# Optocoupler_STM32_REVA.net
KiCad netlist of a schematic drawn in Altium Designer
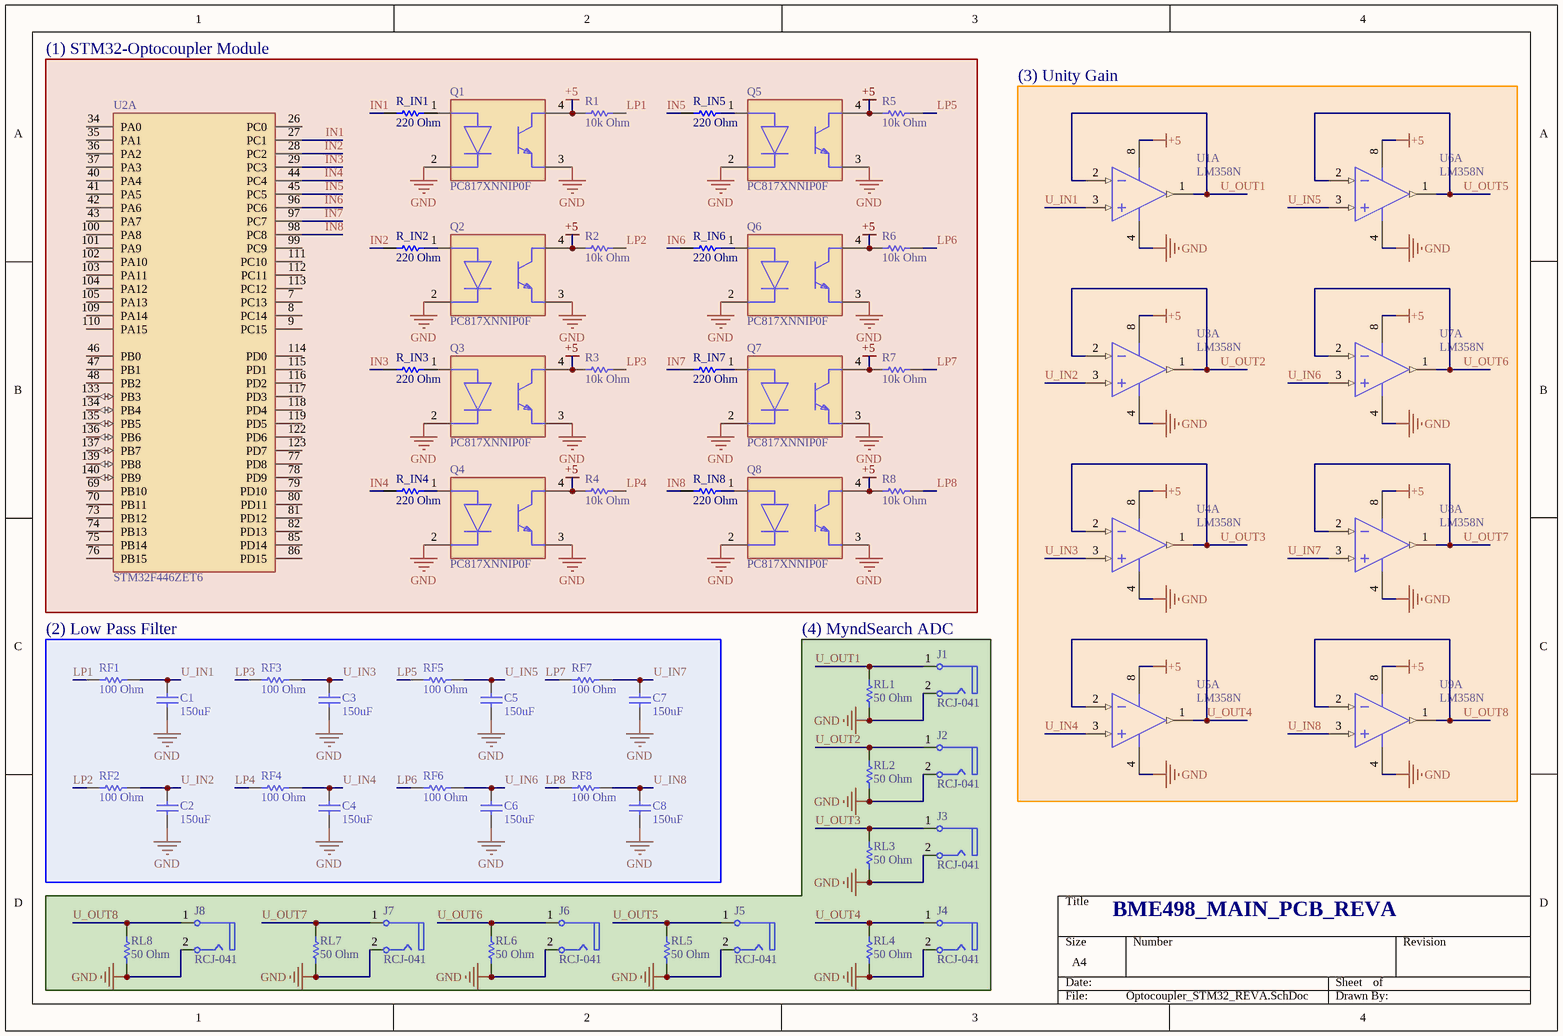
[diagram p0: Optocoupler_STM32_REVA.SchDoc]

(export (version "E")
  (design (tool "Eeschema 10.0.6"))
  (components
    (comp (ref "C1")
      (value "150uF")
      (footprint "RADIAL-0.1")
      (description "Capacitor")
      (fields
        (field (name "MANUFACTURER PART NUMBER") "EEA-GA1C150B")
        (field (name "PUBLISHER") "Altium Limited")
      )
      (libsource (lib "ECE295-Capacitors-TH") (part "CAP ALUM 15UF 20% 16V RADIAL"))
    )
    (comp (ref "C2")
      (value "150uF")
      (footprint "RADIAL-0.1")
      (description "Capacitor")
      (fields
        (field (name "MANUFACTURER PART NUMBER") "EEA-GA1C150B")
        (field (name "PUBLISHER") "Altium Limited")
      )
      (libsource (lib "ECE295-Capacitors-TH") (part "CAP ALUM 15UF 20% 16V RADIAL"))
    )
    (comp (ref "C3")
      (value "150uF")
      (footprint "RADIAL-0.1")
      (description "Capacitor")
      (fields
        (field (name "MANUFACTURER PART NUMBER") "EEA-GA1C150B")
        (field (name "PUBLISHER") "Altium Limited")
      )
      (libsource (lib "ECE295-Capacitors-TH") (part "CAP ALUM 15UF 20% 16V RADIAL"))
    )
    (comp (ref "C4")
      (value "150uF")
      (footprint "RADIAL-0.1")
      (description "Capacitor")
      (fields
        (field (name "MANUFACTURER PART NUMBER") "EEA-GA1C150B")
        (field (name "PUBLISHER") "Altium Limited")
      )
      (libsource (lib "ECE295-Capacitors-TH") (part "CAP ALUM 15UF 20% 16V RADIAL"))
    )
    (comp (ref "C5")
      (value "150uF")
      (footprint "RADIAL-0.1")
      (description "Capacitor")
      (fields
        (field (name "MANUFACTURER PART NUMBER") "EEA-GA1C150B")
        (field (name "PUBLISHER") "Altium Limited")
      )
      (libsource (lib "ECE295-Capacitors-TH") (part "CAP ALUM 15UF 20% 16V RADIAL"))
    )
    (comp (ref "C6")
      (value "150uF")
      (footprint "RADIAL-0.1")
      (description "Capacitor")
      (fields
        (field (name "MANUFACTURER PART NUMBER") "EEA-GA1C150B")
        (field (name "PUBLISHER") "Altium Limited")
      )
      (libsource (lib "ECE295-Capacitors-TH") (part "CAP ALUM 15UF 20% 16V RADIAL"))
    )
    (comp (ref "C7")
      (value "150uF")
      (footprint "RADIAL-0.1")
      (description "Capacitor")
      (fields
        (field (name "MANUFACTURER PART NUMBER") "EEA-GA1C150B")
        (field (name "PUBLISHER") "Altium Limited")
      )
      (libsource (lib "ECE295-Capacitors-TH") (part "CAP ALUM 15UF 20% 16V RADIAL"))
    )
    (comp (ref "C8")
      (value "150uF")
      (footprint "RADIAL-0.1")
      (description "Capacitor")
      (fields
        (field (name "MANUFACTURER PART NUMBER") "EEA-GA1C150B")
        (field (name "PUBLISHER") "Altium Limited")
      )
      (libsource (lib "ECE295-Capacitors-TH") (part "CAP ALUM 15UF 20% 16V RADIAL"))
    )
    (comp (ref "J1")
      (value "RCJ-041")
      (footprint "CUI-RCJ-041_V")
      (description "Female RCJ Jack, 2 Position, Height 11.724 mm, Tail Length 4 mm, RoHS, Bulk")
      (libsource (lib "Altium Content Vault") (part "JACK-2CD2"))
    )
    (comp (ref "J2")
      (value "RCJ-041")
      (footprint "CUI-RCJ-041_V")
      (description "Female RCJ Jack, 2 Position, Height 11.724 mm, Tail Length 4 mm, RoHS, Bulk")
      (libsource (lib "Altium Content Vault") (part "JACK-2CD2"))
    )
    (comp (ref "J3")
      (value "RCJ-041")
      (footprint "CUI-RCJ-041_V")
      (description "Female RCJ Jack, 2 Position, Height 11.724 mm, Tail Length 4 mm, RoHS, Bulk")
      (libsource (lib "Altium Content Vault") (part "JACK-2CD2"))
    )
    (comp (ref "J4")
      (value "RCJ-041")
      (footprint "CUI-RCJ-041_V")
      (description "Female RCJ Jack, 2 Position, Height 11.724 mm, Tail Length 4 mm, RoHS, Bulk")
      (libsource (lib "Altium Content Vault") (part "JACK-2CD2"))
    )
    (comp (ref "J5")
      (value "RCJ-041")
      (footprint "CUI-RCJ-041_V")
      (description "Female RCJ Jack, 2 Position, Height 11.724 mm, Tail Length 4 mm, RoHS, Bulk")
      (libsource (lib "Altium Content Vault") (part "JACK-2CD2"))
    )
    (comp (ref "J6")
      (value "RCJ-041")
      (footprint "CUI-RCJ-041_V")
      (description "Female RCJ Jack, 2 Position, Height 11.724 mm, Tail Length 4 mm, RoHS, Bulk")
      (libsource (lib "Altium Content Vault") (part "JACK-2CD2"))
    )
    (comp (ref "J7")
      (value "RCJ-041")
      (footprint "CUI-RCJ-041_V")
      (description "Female RCJ Jack, 2 Position, Height 11.724 mm, Tail Length 4 mm, RoHS, Bulk")
      (libsource (lib "Altium Content Vault") (part "JACK-2CD2"))
    )
    (comp (ref "J8")
      (value "RCJ-041")
      (footprint "CUI-RCJ-041_V")
      (description "Female RCJ Jack, 2 Position, Height 11.724 mm, Tail Length 4 mm, RoHS, Bulk")
      (libsource (lib "Altium Content Vault") (part "JACK-2CD2"))
    )
    (comp (ref "Q1")
      (value "PC817XNNIP0F")
      (footprint "FP-PC817XNNIP0F-MFG")
      (description "OPTOISOLATOR 5KV TRANS 4SMD")
      (libsource (lib "Altium Content Vault") (part "6470904bf6395c62928ee73e60120b8"))
    )
    (comp (ref "Q2")
      (value "PC817XNNIP0F")
      (footprint "FP-PC817XNNIP0F-MFG")
      (description "OPTOISOLATOR 5KV TRANS 4SMD")
      (libsource (lib "Altium Content Vault") (part "6470904bf6395c62928ee73e60120b8"))
    )
    (comp (ref "Q3")
      (value "PC817XNNIP0F")
      (footprint "FP-PC817XNNIP0F-MFG")
      (description "OPTOISOLATOR 5KV TRANS 4SMD")
      (libsource (lib "Altium Content Vault") (part "6470904bf6395c62928ee73e60120b8"))
    )
    (comp (ref "Q4")
      (value "PC817XNNIP0F")
      (footprint "FP-PC817XNNIP0F-MFG")
      (description "OPTOISOLATOR 5KV TRANS 4SMD")
      (libsource (lib "Altium Content Vault") (part "6470904bf6395c62928ee73e60120b8"))
    )
    (comp (ref "Q5")
      (value "PC817XNNIP0F")
      (footprint "FP-PC817XNNIP0F-MFG")
      (description "OPTOISOLATOR 5KV TRANS 4SMD")
      (libsource (lib "Altium Content Vault") (part "6470904bf6395c62928ee73e60120b8"))
    )
    (comp (ref "Q6")
      (value "PC817XNNIP0F")
      (footprint "FP-PC817XNNIP0F-MFG")
      (description "OPTOISOLATOR 5KV TRANS 4SMD")
      (libsource (lib "Altium Content Vault") (part "6470904bf6395c62928ee73e60120b8"))
    )
    (comp (ref "Q7")
      (value "PC817XNNIP0F")
      (footprint "FP-PC817XNNIP0F-MFG")
      (description "OPTOISOLATOR 5KV TRANS 4SMD")
      (libsource (lib "Altium Content Vault") (part "6470904bf6395c62928ee73e60120b8"))
    )
    (comp (ref "Q8")
      (value "PC817XNNIP0F")
      (footprint "FP-PC817XNNIP0F-MFG")
      (description "OPTOISOLATOR 5KV TRANS 4SMD")
      (libsource (lib "Altium Content Vault") (part "6470904bf6395c62928ee73e60120b8"))
    )
    (comp (ref "R1")
      (value "10k Ohm")
      (footprint "AXIAL-0.3")
      (description "Resistor")
      (fields
        (field (name "MANUFACTURER PART NUMBER") "CFR-25JB-52-10R")
        (field (name "TOLERANCE") "0.05")
        (field (name "PUBLISHER") "Altium Limited")
      )
      (libsource (lib "ECE295-Resistors-TH") (part "RES 10 OHM 5% 1/4W AXIAL"))
    )
    (comp (ref "R2")
      (value "10k Ohm")
      (footprint "AXIAL-0.3")
      (description "Resistor")
      (fields
        (field (name "MANUFACTURER PART NUMBER") "CFR-25JB-52-10R")
        (field (name "TOLERANCE") "0.05")
        (field (name "PUBLISHER") "Altium Limited")
      )
      (libsource (lib "ECE295-Resistors-TH") (part "RES 10 OHM 5% 1/4W AXIAL"))
    )
    (comp (ref "R3")
      (value "10k Ohm")
      (footprint "AXIAL-0.3")
      (description "Resistor")
      (fields
        (field (name "MANUFACTURER PART NUMBER") "CFR-25JB-52-10R")
        (field (name "TOLERANCE") "0.05")
        (field (name "PUBLISHER") "Altium Limited")
      )
      (libsource (lib "ECE295-Resistors-TH") (part "RES 10 OHM 5% 1/4W AXIAL"))
    )
    (comp (ref "R4")
      (value "10k Ohm")
      (footprint "AXIAL-0.3")
      (description "Resistor")
      (fields
        (field (name "MANUFACTURER PART NUMBER") "CFR-25JB-52-10R")
        (field (name "TOLERANCE") "0.05")
        (field (name "PUBLISHER") "Altium Limited")
      )
      (libsource (lib "ECE295-Resistors-TH") (part "RES 10 OHM 5% 1/4W AXIAL"))
    )
    (comp (ref "R5")
      (value "10k Ohm")
      (footprint "AXIAL-0.3")
      (description "Resistor")
      (fields
        (field (name "MANUFACTURER PART NUMBER") "CFR-25JB-52-10R")
        (field (name "TOLERANCE") "0.05")
        (field (name "PUBLISHER") "Altium Limited")
      )
      (libsource (lib "ECE295-Resistors-TH") (part "RES 10 OHM 5% 1/4W AXIAL"))
    )
    (comp (ref "R6")
      (value "10k Ohm")
      (footprint "AXIAL-0.3")
      (description "Resistor")
      (fields
        (field (name "MANUFACTURER PART NUMBER") "CFR-25JB-52-10R")
        (field (name "TOLERANCE") "0.05")
        (field (name "PUBLISHER") "Altium Limited")
      )
      (libsource (lib "ECE295-Resistors-TH") (part "RES 10 OHM 5% 1/4W AXIAL"))
    )
    (comp (ref "R7")
      (value "10k Ohm")
      (footprint "AXIAL-0.3")
      (description "Resistor")
      (fields
        (field (name "MANUFACTURER PART NUMBER") "CFR-25JB-52-10R")
        (field (name "TOLERANCE") "0.05")
        (field (name "PUBLISHER") "Altium Limited")
      )
      (libsource (lib "ECE295-Resistors-TH") (part "RES 10 OHM 5% 1/4W AXIAL"))
    )
    (comp (ref "R8")
      (value "10k Ohm")
      (footprint "AXIAL-0.3")
      (description "Resistor")
      (fields
        (field (name "MANUFACTURER PART NUMBER") "CFR-25JB-52-10R")
        (field (name "TOLERANCE") "0.05")
        (field (name "PUBLISHER") "Altium Limited")
      )
      (libsource (lib "ECE295-Resistors-TH") (part "RES 10 OHM 5% 1/4W AXIAL"))
    )
    (comp (ref "RF1")
      (value "100 Ohm")
      (footprint "AXIAL-0.3")
      (description "Resistor")
      (fields
        (field (name "MANUFACTURER PART NUMBER") "CFR-25JB-52-10R")
        (field (name "TOLERANCE") "0.05")
        (field (name "PUBLISHER") "Altium Limited")
      )
      (libsource (lib "ECE295-Resistors-TH") (part "RES 10 OHM 5% 1/4W AXIAL"))
    )
    (comp (ref "RF2")
      (value "100 Ohm")
      (footprint "AXIAL-0.3")
      (description "Resistor")
      (fields
        (field (name "MANUFACTURER PART NUMBER") "CFR-25JB-52-10R")
        (field (name "TOLERANCE") "0.05")
        (field (name "PUBLISHER") "Altium Limited")
      )
      (libsource (lib "ECE295-Resistors-TH") (part "RES 10 OHM 5% 1/4W AXIAL"))
    )
    (comp (ref "RF3")
      (value "100 Ohm")
      (footprint "AXIAL-0.3")
      (description "Resistor")
      (fields
        (field (name "MANUFACTURER PART NUMBER") "CFR-25JB-52-10R")
        (field (name "TOLERANCE") "0.05")
        (field (name "PUBLISHER") "Altium Limited")
      )
      (libsource (lib "ECE295-Resistors-TH") (part "RES 10 OHM 5% 1/4W AXIAL"))
    )
    (comp (ref "RF4")
      (value "100 Ohm")
      (footprint "AXIAL-0.3")
      (description "Resistor")
      (fields
        (field (name "MANUFACTURER PART NUMBER") "CFR-25JB-52-10R")
        (field (name "TOLERANCE") "0.05")
        (field (name "PUBLISHER") "Altium Limited")
      )
      (libsource (lib "ECE295-Resistors-TH") (part "RES 10 OHM 5% 1/4W AXIAL"))
    )
    (comp (ref "RF5")
      (value "100 Ohm")
      (footprint "AXIAL-0.3")
      (description "Resistor")
      (fields
        (field (name "MANUFACTURER PART NUMBER") "CFR-25JB-52-10R")
        (field (name "TOLERANCE") "0.05")
        (field (name "PUBLISHER") "Altium Limited")
      )
      (libsource (lib "ECE295-Resistors-TH") (part "RES 10 OHM 5% 1/4W AXIAL"))
    )
    (comp (ref "RF6")
      (value "100 Ohm")
      (footprint "AXIAL-0.3")
      (description "Resistor")
      (fields
        (field (name "MANUFACTURER PART NUMBER") "CFR-25JB-52-10R")
        (field (name "TOLERANCE") "0.05")
        (field (name "PUBLISHER") "Altium Limited")
      )
      (libsource (lib "ECE295-Resistors-TH") (part "RES 10 OHM 5% 1/4W AXIAL"))
    )
    (comp (ref "RF7")
      (value "100 Ohm")
      (footprint "AXIAL-0.3")
      (description "Resistor")
      (fields
        (field (name "MANUFACTURER PART NUMBER") "CFR-25JB-52-10R")
        (field (name "TOLERANCE") "0.05")
        (field (name "PUBLISHER") "Altium Limited")
      )
      (libsource (lib "ECE295-Resistors-TH") (part "RES 10 OHM 5% 1/4W AXIAL"))
    )
    (comp (ref "RF8")
      (value "100 Ohm")
      (footprint "AXIAL-0.3")
      (description "Resistor")
      (fields
        (field (name "MANUFACTURER PART NUMBER") "CFR-25JB-52-10R")
        (field (name "TOLERANCE") "0.05")
        (field (name "PUBLISHER") "Altium Limited")
      )
      (libsource (lib "ECE295-Resistors-TH") (part "RES 10 OHM 5% 1/4W AXIAL"))
    )
    (comp (ref "RL1")
      (value "50 Ohm")
      (footprint "AXIAL-0.3")
      (description "Resistor")
      (fields
        (field (name "MANUFACTURER PART NUMBER") "CFR-25JB-52-10R")
        (field (name "TOLERANCE") "0.05")
        (field (name "PUBLISHER") "Altium Limited")
      )
      (libsource (lib "ECE295-Resistors-TH") (part "RES 10 OHM 5% 1/4W AXIAL"))
    )
    (comp (ref "RL2")
      (value "50 Ohm")
      (footprint "AXIAL-0.3")
      (description "Resistor")
      (fields
        (field (name "MANUFACTURER PART NUMBER") "CFR-25JB-52-10R")
        (field (name "TOLERANCE") "0.05")
        (field (name "PUBLISHER") "Altium Limited")
      )
      (libsource (lib "ECE295-Resistors-TH") (part "RES 10 OHM 5% 1/4W AXIAL"))
    )
    (comp (ref "RL3")
      (value "50 Ohm")
      (footprint "AXIAL-0.3")
      (description "Resistor")
      (fields
        (field (name "MANUFACTURER PART NUMBER") "CFR-25JB-52-10R")
        (field (name "TOLERANCE") "0.05")
        (field (name "PUBLISHER") "Altium Limited")
      )
      (libsource (lib "ECE295-Resistors-TH") (part "RES 10 OHM 5% 1/4W AXIAL"))
    )
    (comp (ref "RL4")
      (value "50 Ohm")
      (footprint "AXIAL-0.3")
      (description "Resistor")
      (fields
        (field (name "MANUFACTURER PART NUMBER") "CFR-25JB-52-10R")
        (field (name "TOLERANCE") "0.05")
        (field (name "PUBLISHER") "Altium Limited")
      )
      (libsource (lib "ECE295-Resistors-TH") (part "RES 10 OHM 5% 1/4W AXIAL"))
    )
    (comp (ref "RL5")
      (value "50 Ohm")
      (footprint "AXIAL-0.3")
      (description "Resistor")
      (fields
        (field (name "MANUFACTURER PART NUMBER") "CFR-25JB-52-10R")
        (field (name "TOLERANCE") "0.05")
        (field (name "PUBLISHER") "Altium Limited")
      )
      (libsource (lib "ECE295-Resistors-TH") (part "RES 10 OHM 5% 1/4W AXIAL"))
    )
    (comp (ref "RL6")
      (value "50 Ohm")
      (footprint "AXIAL-0.3")
      (description "Resistor")
      (fields
        (field (name "MANUFACTURER PART NUMBER") "CFR-25JB-52-10R")
        (field (name "TOLERANCE") "0.05")
        (field (name "PUBLISHER") "Altium Limited")
      )
      (libsource (lib "ECE295-Resistors-TH") (part "RES 10 OHM 5% 1/4W AXIAL"))
    )
    (comp (ref "RL7")
      (value "50 Ohm")
      (footprint "AXIAL-0.3")
      (description "Resistor")
      (fields
        (field (name "MANUFACTURER PART NUMBER") "CFR-25JB-52-10R")
        (field (name "TOLERANCE") "0.05")
        (field (name "PUBLISHER") "Altium Limited")
      )
      (libsource (lib "ECE295-Resistors-TH") (part "RES 10 OHM 5% 1/4W AXIAL"))
    )
    (comp (ref "RL8")
      (value "50 Ohm")
      (footprint "AXIAL-0.3")
      (description "Resistor")
      (fields
        (field (name "MANUFACTURER PART NUMBER") "CFR-25JB-52-10R")
        (field (name "TOLERANCE") "0.05")
        (field (name "PUBLISHER") "Altium Limited")
      )
      (libsource (lib "ECE295-Resistors-TH") (part "RES 10 OHM 5% 1/4W AXIAL"))
    )
    (comp (ref "R_IN1")
      (value "220 Ohm")
      (footprint "AXIAL-0.3")
      (description "Resistor")
      (fields
        (field (name "MANUFACTURER PART NUMBER") "CFR-25JB-52-10R")
        (field (name "TOLERANCE") "0.05")
        (field (name "PUBLISHER") "Altium Limited")
      )
      (libsource (lib "ECE295-Resistors-TH") (part "RES 10 OHM 5% 1/4W AXIAL"))
    )
    (comp (ref "R_IN2")
      (value "220 Ohm")
      (footprint "AXIAL-0.3")
      (description "Resistor")
      (fields
        (field (name "MANUFACTURER PART NUMBER") "CFR-25JB-52-10R")
        (field (name "TOLERANCE") "0.05")
        (field (name "PUBLISHER") "Altium Limited")
      )
      (libsource (lib "ECE295-Resistors-TH") (part "RES 10 OHM 5% 1/4W AXIAL"))
    )
    (comp (ref "R_IN3")
      (value "220 Ohm")
      (footprint "AXIAL-0.3")
      (description "Resistor")
      (fields
        (field (name "MANUFACTURER PART NUMBER") "CFR-25JB-52-10R")
        (field (name "TOLERANCE") "0.05")
        (field (name "PUBLISHER") "Altium Limited")
      )
      (libsource (lib "ECE295-Resistors-TH") (part "RES 10 OHM 5% 1/4W AXIAL"))
    )
    (comp (ref "R_IN4")
      (value "220 Ohm")
      (footprint "AXIAL-0.3")
      (description "Resistor")
      (fields
        (field (name "MANUFACTURER PART NUMBER") "CFR-25JB-52-10R")
        (field (name "TOLERANCE") "0.05")
        (field (name "PUBLISHER") "Altium Limited")
      )
      (libsource (lib "ECE295-Resistors-TH") (part "RES 10 OHM 5% 1/4W AXIAL"))
    )
    (comp (ref "R_IN5")
      (value "220 Ohm")
      (footprint "AXIAL-0.3")
      (description "Resistor")
      (fields
        (field (name "MANUFACTURER PART NUMBER") "CFR-25JB-52-10R")
        (field (name "TOLERANCE") "0.05")
        (field (name "PUBLISHER") "Altium Limited")
      )
      (libsource (lib "ECE295-Resistors-TH") (part "RES 10 OHM 5% 1/4W AXIAL"))
    )
    (comp (ref "R_IN6")
      (value "220 Ohm")
      (footprint "AXIAL-0.3")
      (description "Resistor")
      (fields
        (field (name "MANUFACTURER PART NUMBER") "CFR-25JB-52-10R")
        (field (name "TOLERANCE") "0.05")
        (field (name "PUBLISHER") "Altium Limited")
      )
      (libsource (lib "ECE295-Resistors-TH") (part "RES 10 OHM 5% 1/4W AXIAL"))
    )
    (comp (ref "R_IN7")
      (value "220 Ohm")
      (footprint "AXIAL-0.3")
      (description "Resistor")
      (fields
        (field (name "MANUFACTURER PART NUMBER") "CFR-25JB-52-10R")
        (field (name "TOLERANCE") "0.05")
        (field (name "PUBLISHER") "Altium Limited")
      )
      (libsource (lib "ECE295-Resistors-TH") (part "RES 10 OHM 5% 1/4W AXIAL"))
    )
    (comp (ref "R_IN8")
      (value "220 Ohm")
      (footprint "AXIAL-0.3")
      (description "Resistor")
      (fields
        (field (name "MANUFACTURER PART NUMBER") "CFR-25JB-52-10R")
        (field (name "TOLERANCE") "0.05")
        (field (name "PUBLISHER") "Altium Limited")
      )
      (libsource (lib "ECE295-Resistors-TH") (part "RES 10 OHM 5% 1/4W AXIAL"))
    )
    (comp (ref "U1")
      (value "LM358N")
      (footprint "ONSC-PDIP-8-626-05_M")
      (description "Single Supply Dual Operational Amplifier, 3 to 32 V, 0 to 70 degC, 8-Pin PDIP, Tube")
      (fields (field (name "MANUFACTURER") "On Semiconductor"))
      (libsource (lib "Altium Content Vault") (part "ONSC-LM358_NCV2904-8"))
    )
    (comp (ref "U2")
      (value "STM32F446ZET6")
      (footprint "FP-STM32F446ZET6-MFG")
      (description "IC MCU 32BIT 512KB FLASH 144LQFP")
      (fields
        (field (name "OCTOPART") "https://octopart.com/stm32f446zet6-stmicroelectronics-52642927")
        (field (name "MANUFACTURER") "STMicroelectronics")
      )
      (libsource (lib "Altium Content Vault") (part "a0fab8d4e0431f78458e0514a03e2d2"))
    )
    (comp (ref "U3")
      (value "LM358N")
      (footprint "ONSC-PDIP-8-626-05_M")
      (description "Single Supply Dual Operational Amplifier, 3 to 32 V, 0 to 70 degC, 8-Pin PDIP, Tube")
      (fields (field (name "MANUFACTURER") "On Semiconductor"))
      (libsource (lib "Altium Content Vault") (part "ONSC-LM358_NCV2904-8"))
    )
    (comp (ref "U4")
      (value "LM358N")
      (footprint "ONSC-PDIP-8-626-05_M")
      (description "Single Supply Dual Operational Amplifier, 3 to 32 V, 0 to 70 degC, 8-Pin PDIP, Tube")
      (fields (field (name "MANUFACTURER") "On Semiconductor"))
      (libsource (lib "Altium Content Vault") (part "ONSC-LM358_NCV2904-8"))
    )
    (comp (ref "U5")
      (value "LM358N")
      (footprint "ONSC-PDIP-8-626-05_M")
      (description "Single Supply Dual Operational Amplifier, 3 to 32 V, 0 to 70 degC, 8-Pin PDIP, Tube")
      (fields (field (name "MANUFACTURER") "On Semiconductor"))
      (libsource (lib "Altium Content Vault") (part "ONSC-LM358_NCV2904-8"))
    )
    (comp (ref "U6")
      (value "LM358N")
      (footprint "ONSC-PDIP-8-626-05_M")
      (description "Single Supply Dual Operational Amplifier, 3 to 32 V, 0 to 70 degC, 8-Pin PDIP, Tube")
      (fields (field (name "MANUFACTURER") "On Semiconductor"))
      (libsource (lib "Altium Content Vault") (part "ONSC-LM358_NCV2904-8"))
    )
    (comp (ref "U7")
      (value "LM358N")
      (footprint "ONSC-PDIP-8-626-05_M")
      (description "Single Supply Dual Operational Amplifier, 3 to 32 V, 0 to 70 degC, 8-Pin PDIP, Tube")
      (fields (field (name "MANUFACTURER") "On Semiconductor"))
      (libsource (lib "Altium Content Vault") (part "ONSC-LM358_NCV2904-8"))
    )
    (comp (ref "U8")
      (value "LM358N")
      (footprint "ONSC-PDIP-8-626-05_M")
      (description "Single Supply Dual Operational Amplifier, 3 to 32 V, 0 to 70 degC, 8-Pin PDIP, Tube")
      (fields (field (name "MANUFACTURER") "On Semiconductor"))
      (libsource (lib "Altium Content Vault") (part "ONSC-LM358_NCV2904-8"))
    )
    (comp (ref "U9")
      (value "LM358N")
      (footprint "ONSC-PDIP-8-626-05_M")
      (description "Single Supply Dual Operational Amplifier, 3 to 32 V, 0 to 70 degC, 8-Pin PDIP, Tube")
      (fields (field (name "MANUFACTURER") "On Semiconductor"))
      (libsource (lib "Altium Content Vault") (part "ONSC-LM358_NCV2904-8"))
    )
  )
  (nets
    (net (code "1") (name "+5") (class "Default")
      (node (ref "Q1") (pin "4") (pinfunction "C_4") (pintype "passive"))
      (node (ref "Q2") (pin "4") (pinfunction "C_4") (pintype "passive"))
      (node (ref "Q3") (pin "4") (pinfunction "C_4") (pintype "passive"))
      (node (ref "Q4") (pin "4") (pinfunction "C_4") (pintype "passive"))
      (node (ref "Q5") (pin "4") (pinfunction "C_4") (pintype "passive"))
      (node (ref "Q6") (pin "4") (pinfunction "C_4") (pintype "passive"))
      (node (ref "Q7") (pin "4") (pinfunction "C_4") (pintype "passive"))
      (node (ref "Q8") (pin "4") (pinfunction "C_4") (pintype "passive"))
      (node (ref "R1") (pin "1") (pinfunction "1_1") (pintype "passive"))
      (node (ref "R2") (pin "1") (pinfunction "1_1") (pintype "passive"))
      (node (ref "R3") (pin "1") (pinfunction "1_1") (pintype "passive"))
      (node (ref "R4") (pin "1") (pinfunction "1_1") (pintype "passive"))
      (node (ref "R5") (pin "1") (pinfunction "1_1") (pintype "passive"))
      (node (ref "R6") (pin "1") (pinfunction "1_1") (pintype "passive"))
      (node (ref "R7") (pin "1") (pinfunction "1_1") (pintype "passive"))
      (node (ref "R8") (pin "1") (pinfunction "1_1") (pintype "passive"))
      (node (ref "U1") (pin "8") (pinfunction "VCC_8") (pintype "power_in"))
      (node (ref "U3") (pin "8") (pinfunction "VCC_8") (pintype "power_in"))
      (node (ref "U4") (pin "8") (pinfunction "VCC_8") (pintype "power_in"))
      (node (ref "U5") (pin "8") (pinfunction "VCC_8") (pintype "power_in"))
      (node (ref "U6") (pin "8") (pinfunction "VCC_8") (pintype "power_in"))
      (node (ref "U7") (pin "8") (pinfunction "VCC_8") (pintype "power_in"))
      (node (ref "U8") (pin "8") (pinfunction "VCC_8") (pintype "power_in"))
      (node (ref "U9") (pin "8") (pinfunction "VCC_8") (pintype "power_in"))
    )
    (net (code "2") (name "/IN1") (class "Default")
      (node (ref "R_IN1") (pin "2") (pinfunction "2_2") (pintype "passive"))
      (node (ref "U2") (pin "27") (pinfunction "PC1_27") (pintype "passive"))
    )
    (net (code "3") (name "/IN2") (class "Default")
      (node (ref "R_IN2") (pin "2") (pinfunction "2_2") (pintype "passive"))
      (node (ref "U2") (pin "28") (pinfunction "PC2_28") (pintype "passive"))
    )
    (net (code "4") (name "/IN3") (class "Default")
      (node (ref "R_IN3") (pin "2") (pinfunction "2_2") (pintype "passive"))
      (node (ref "U2") (pin "29") (pinfunction "PC3_29") (pintype "passive"))
    )
    (net (code "5") (name "/IN4") (class "Default")
      (node (ref "R_IN4") (pin "2") (pinfunction "2_2") (pintype "passive"))
      (node (ref "U2") (pin "44") (pinfunction "PC4_44") (pintype "passive"))
    )
    (net (code "6") (name "/IN5") (class "Default")
      (node (ref "R_IN5") (pin "2") (pinfunction "2_2") (pintype "passive"))
      (node (ref "U2") (pin "45") (pinfunction "PC5_45") (pintype "passive"))
    )
    (net (code "7") (name "/IN6") (class "Default")
      (node (ref "R_IN6") (pin "2") (pinfunction "2_2") (pintype "passive"))
      (node (ref "U2") (pin "96") (pinfunction "PC6_96") (pintype "passive"))
    )
    (net (code "8") (name "/IN7") (class "Default")
      (node (ref "R_IN7") (pin "2") (pinfunction "2_2") (pintype "passive"))
      (node (ref "U2") (pin "97") (pinfunction "PC7_97") (pintype "passive"))
    )
    (net (code "9") (name "/IN8") (class "Default")
      (node (ref "R_IN8") (pin "2") (pinfunction "2_2") (pintype "passive"))
      (node (ref "U2") (pin "98") (pinfunction "PC8_98") (pintype "passive"))
    )
    (net (code "10") (name "/LP1") (class "Default")
      (node (ref "R1") (pin "2") (pinfunction "2_2") (pintype "passive"))
      (node (ref "RF1") (pin "1") (pinfunction "1_1") (pintype "passive"))
    )
    (net (code "11") (name "/LP2") (class "Default")
      (node (ref "R2") (pin "2") (pinfunction "2_2") (pintype "passive"))
      (node (ref "RF2") (pin "1") (pinfunction "1_1") (pintype "passive"))
    )
    (net (code "12") (name "/LP3") (class "Default")
      (node (ref "R3") (pin "2") (pinfunction "2_2") (pintype "passive"))
      (node (ref "RF3") (pin "1") (pinfunction "1_1") (pintype "passive"))
    )
    (net (code "13") (name "/LP4") (class "Default")
      (node (ref "R4") (pin "2") (pinfunction "2_2") (pintype "passive"))
      (node (ref "RF4") (pin "1") (pinfunction "1_1") (pintype "passive"))
    )
    (net (code "14") (name "/LP5") (class "Default")
      (node (ref "R5") (pin "2") (pinfunction "2_2") (pintype "passive"))
      (node (ref "RF5") (pin "1") (pinfunction "1_1") (pintype "passive"))
    )
    (net (code "15") (name "/LP6") (class "Default")
      (node (ref "R6") (pin "2") (pinfunction "2_2") (pintype "passive"))
      (node (ref "RF6") (pin "1") (pinfunction "1_1") (pintype "passive"))
    )
    (net (code "16") (name "/LP7") (class "Default")
      (node (ref "R7") (pin "2") (pinfunction "2_2") (pintype "passive"))
      (node (ref "RF7") (pin "1") (pinfunction "1_1") (pintype "passive"))
    )
    (net (code "17") (name "/LP8") (class "Default")
      (node (ref "R8") (pin "2") (pinfunction "2_2") (pintype "passive"))
      (node (ref "RF8") (pin "1") (pinfunction "1_1") (pintype "passive"))
    )
    (net (code "18") (name "/U_IN1") (class "Default")
      (node (ref "C1") (pin "2") (pinfunction "2_2") (pintype "passive"))
      (node (ref "RF1") (pin "2") (pinfunction "2_2") (pintype "passive"))
      (node (ref "U1") (pin "3") (pinfunction "INA+_3") (pintype "input"))
    )
    (net (code "19") (name "/U_IN2") (class "Default")
      (node (ref "C2") (pin "2") (pinfunction "2_2") (pintype "passive"))
      (node (ref "RF2") (pin "2") (pinfunction "2_2") (pintype "passive"))
      (node (ref "U3") (pin "3") (pinfunction "INA+_3") (pintype "input"))
    )
    (net (code "20") (name "/U_IN3") (class "Default")
      (node (ref "C3") (pin "2") (pinfunction "2_2") (pintype "passive"))
      (node (ref "RF3") (pin "2") (pinfunction "2_2") (pintype "passive"))
      (node (ref "U4") (pin "3") (pinfunction "INA+_3") (pintype "input"))
    )
    (net (code "21") (name "/U_IN4") (class "Default")
      (node (ref "C4") (pin "2") (pinfunction "2_2") (pintype "passive"))
      (node (ref "RF4") (pin "2") (pinfunction "2_2") (pintype "passive"))
      (node (ref "U5") (pin "3") (pinfunction "INA+_3") (pintype "input"))
    )
    (net (code "22") (name "/U_IN5") (class "Default")
      (node (ref "C5") (pin "2") (pinfunction "2_2") (pintype "passive"))
      (node (ref "RF5") (pin "2") (pinfunction "2_2") (pintype "passive"))
      (node (ref "U6") (pin "3") (pinfunction "INA+_3") (pintype "input"))
    )
    (net (code "23") (name "/U_IN6") (class "Default")
      (node (ref "C6") (pin "2") (pinfunction "2_2") (pintype "passive"))
      (node (ref "RF6") (pin "2") (pinfunction "2_2") (pintype "passive"))
      (node (ref "U7") (pin "3") (pinfunction "INA+_3") (pintype "input"))
    )
    (net (code "24") (name "/U_IN7") (class "Default")
      (node (ref "C7") (pin "2") (pinfunction "2_2") (pintype "passive"))
      (node (ref "RF7") (pin "2") (pinfunction "2_2") (pintype "passive"))
      (node (ref "U8") (pin "3") (pinfunction "INA+_3") (pintype "input"))
    )
    (net (code "25") (name "/U_IN8") (class "Default")
      (node (ref "C8") (pin "2") (pinfunction "2_2") (pintype "passive"))
      (node (ref "RF8") (pin "2") (pinfunction "2_2") (pintype "passive"))
      (node (ref "U9") (pin "3") (pinfunction "INA+_3") (pintype "input"))
    )
    (net (code "26") (name "/U_OUT1") (class "Default")
      (node (ref "J1") (pin "1") (pinfunction "1_1") (pintype "passive"))
      (node (ref "RL1") (pin "2") (pinfunction "2_2") (pintype "passive"))
      (node (ref "U1") (pin "1") (pinfunction "OUTA_1") (pintype "output"))
      (node (ref "U1") (pin "2") (pinfunction "INA-_2") (pintype "input"))
    )
    (net (code "27") (name "/U_OUT2") (class "Default")
      (node (ref "J2") (pin "1") (pinfunction "1_1") (pintype "passive"))
      (node (ref "RL2") (pin "2") (pinfunction "2_2") (pintype "passive"))
      (node (ref "U3") (pin "1") (pinfunction "OUTA_1") (pintype "output"))
      (node (ref "U3") (pin "2") (pinfunction "INA-_2") (pintype "input"))
    )
    (net (code "28") (name "/U_OUT3") (class "Default")
      (node (ref "J3") (pin "1") (pinfunction "1_1") (pintype "passive"))
      (node (ref "RL3") (pin "2") (pinfunction "2_2") (pintype "passive"))
      (node (ref "U4") (pin "1") (pinfunction "OUTA_1") (pintype "output"))
      (node (ref "U4") (pin "2") (pinfunction "INA-_2") (pintype "input"))
    )
    (net (code "29") (name "/U_OUT4") (class "Default")
      (node (ref "J4") (pin "1") (pinfunction "1_1") (pintype "passive"))
      (node (ref "RL4") (pin "2") (pinfunction "2_2") (pintype "passive"))
      (node (ref "U5") (pin "1") (pinfunction "OUTA_1") (pintype "output"))
      (node (ref "U5") (pin "2") (pinfunction "INA-_2") (pintype "input"))
    )
    (net (code "30") (name "/U_OUT5") (class "Default")
      (node (ref "J5") (pin "1") (pinfunction "1_1") (pintype "passive"))
      (node (ref "RL5") (pin "2") (pinfunction "2_2") (pintype "passive"))
      (node (ref "U6") (pin "1") (pinfunction "OUTA_1") (pintype "output"))
      (node (ref "U6") (pin "2") (pinfunction "INA-_2") (pintype "input"))
    )
    (net (code "31") (name "/U_OUT6") (class "Default")
      (node (ref "J6") (pin "1") (pinfunction "1_1") (pintype "passive"))
      (node (ref "RL6") (pin "2") (pinfunction "2_2") (pintype "passive"))
      (node (ref "U7") (pin "1") (pinfunction "OUTA_1") (pintype "output"))
      (node (ref "U7") (pin "2") (pinfunction "INA-_2") (pintype "input"))
    )
    (net (code "32") (name "/U_OUT7") (class "Default")
      (node (ref "J7") (pin "1") (pinfunction "1_1") (pintype "passive"))
      (node (ref "RL7") (pin "2") (pinfunction "2_2") (pintype "passive"))
      (node (ref "U8") (pin "1") (pinfunction "OUTA_1") (pintype "output"))
      (node (ref "U8") (pin "2") (pinfunction "INA-_2") (pintype "input"))
    )
    (net (code "33") (name "/U_OUT8") (class "Default")
      (node (ref "J8") (pin "1") (pinfunction "1_1") (pintype "passive"))
      (node (ref "RL8") (pin "2") (pinfunction "2_2") (pintype "passive"))
      (node (ref "U9") (pin "1") (pinfunction "OUTA_1") (pintype "output"))
      (node (ref "U9") (pin "2") (pinfunction "INA-_2") (pintype "input"))
    )
    (net (code "34") (name "GND") (class "Default")
      (node (ref "C1") (pin "1") (pinfunction "1_1") (pintype "passive"))
      (node (ref "C2") (pin "1") (pinfunction "1_1") (pintype "passive"))
      (node (ref "C3") (pin "1") (pinfunction "1_1") (pintype "passive"))
      (node (ref "C4") (pin "1") (pinfunction "1_1") (pintype "passive"))
      (node (ref "C5") (pin "1") (pinfunction "1_1") (pintype "passive"))
      (node (ref "C6") (pin "1") (pinfunction "1_1") (pintype "passive"))
      (node (ref "C7") (pin "1") (pinfunction "1_1") (pintype "passive"))
      (node (ref "C8") (pin "1") (pinfunction "1_1") (pintype "passive"))
      (node (ref "J1") (pin "2") (pinfunction "2_2") (pintype "passive"))
      (node (ref "J2") (pin "2") (pinfunction "2_2") (pintype "passive"))
      (node (ref "J3") (pin "2") (pinfunction "2_2") (pintype "passive"))
      (node (ref "J4") (pin "2") (pinfunction "2_2") (pintype "passive"))
      (node (ref "J5") (pin "2") (pinfunction "2_2") (pintype "passive"))
      (node (ref "J6") (pin "2") (pinfunction "2_2") (pintype "passive"))
      (node (ref "J7") (pin "2") (pinfunction "2_2") (pintype "passive"))
      (node (ref "J8") (pin "2") (pinfunction "2_2") (pintype "passive"))
      (node (ref "Q1") (pin "2") (pinfunction "C_2") (pintype "passive"))
      (node (ref "Q1") (pin "3") (pinfunction "E_3") (pintype "passive"))
      (node (ref "Q2") (pin "2") (pinfunction "C_2") (pintype "passive"))
      (node (ref "Q2") (pin "3") (pinfunction "E_3") (pintype "passive"))
      (node (ref "Q3") (pin "2") (pinfunction "C_2") (pintype "passive"))
      (node (ref "Q3") (pin "3") (pinfunction "E_3") (pintype "passive"))
      (node (ref "Q4") (pin "2") (pinfunction "C_2") (pintype "passive"))
      (node (ref "Q4") (pin "3") (pinfunction "E_3") (pintype "passive"))
      (node (ref "Q5") (pin "2") (pinfunction "C_2") (pintype "passive"))
      (node (ref "Q5") (pin "3") (pinfunction "E_3") (pintype "passive"))
      (node (ref "Q6") (pin "2") (pinfunction "C_2") (pintype "passive"))
      (node (ref "Q6") (pin "3") (pinfunction "E_3") (pintype "passive"))
      (node (ref "Q7") (pin "2") (pinfunction "C_2") (pintype "passive"))
      (node (ref "Q7") (pin "3") (pinfunction "E_3") (pintype "passive"))
      (node (ref "Q8") (pin "2") (pinfunction "C_2") (pintype "passive"))
      (node (ref "Q8") (pin "3") (pinfunction "E_3") (pintype "passive"))
      (node (ref "RL1") (pin "1") (pinfunction "1_1") (pintype "passive"))
      (node (ref "RL2") (pin "1") (pinfunction "1_1") (pintype "passive"))
      (node (ref "RL3") (pin "1") (pinfunction "1_1") (pintype "passive"))
      (node (ref "RL4") (pin "1") (pinfunction "1_1") (pintype "passive"))
      (node (ref "RL5") (pin "1") (pinfunction "1_1") (pintype "passive"))
      (node (ref "RL6") (pin "1") (pinfunction "1_1") (pintype "passive"))
      (node (ref "RL7") (pin "1") (pinfunction "1_1") (pintype "passive"))
      (node (ref "RL8") (pin "1") (pinfunction "1_1") (pintype "passive"))
      (node (ref "U1") (pin "4") (pinfunction "VEE/GND_4") (pintype "power_in"))
      (node (ref "U3") (pin "4") (pinfunction "VEE/GND_4") (pintype "power_in"))
      (node (ref "U4") (pin "4") (pinfunction "VEE/GND_4") (pintype "power_in"))
      (node (ref "U5") (pin "4") (pinfunction "VEE/GND_4") (pintype "power_in"))
      (node (ref "U6") (pin "4") (pinfunction "VEE/GND_4") (pintype "power_in"))
      (node (ref "U7") (pin "4") (pinfunction "VEE/GND_4") (pintype "power_in"))
      (node (ref "U8") (pin "4") (pinfunction "VEE/GND_4") (pintype "power_in"))
      (node (ref "U9") (pin "4") (pinfunction "VEE/GND_4") (pintype "power_in"))
    )
    (net (code "35") (name "Net-(Q2-A)") (class "Default")
      (node (ref "Q2") (pin "1") (pinfunction "A_1") (pintype "passive"))
      (node (ref "R_IN2") (pin "1") (pinfunction "1_1") (pintype "passive"))
    )
    (net (code "36") (name "Net-(Q4-A)") (class "Default")
      (node (ref "Q4") (pin "1") (pinfunction "A_1") (pintype "passive"))
      (node (ref "R_IN4") (pin "1") (pinfunction "1_1") (pintype "passive"))
    )
    (net (code "37") (name "Net-(Q5-A)") (class "Default")
      (node (ref "Q5") (pin "1") (pinfunction "A_1") (pintype "passive"))
      (node (ref "R_IN5") (pin "1") (pinfunction "1_1") (pintype "passive"))
    )
    (net (code "38") (name "Net-(Q6-A)") (class "Default")
      (node (ref "Q6") (pin "1") (pinfunction "A_1") (pintype "passive"))
      (node (ref "R_IN6") (pin "1") (pinfunction "1_1") (pintype "passive"))
    )
    (net (code "39") (name "Net-(Q7-A)") (class "Default")
      (node (ref "Q7") (pin "1") (pinfunction "A_1") (pintype "passive"))
      (node (ref "R_IN7") (pin "1") (pinfunction "1_1") (pintype "passive"))
    )
    (net (code "40") (name "Net-(Q8-A)") (class "Default")
      (node (ref "Q8") (pin "1") (pinfunction "A_1") (pintype "passive"))
      (node (ref "R_IN8") (pin "1") (pinfunction "1_1") (pintype "passive"))
    )
    (net (code "41") (name "unconnected-(Q1-A-Pad1)") (class "Default")
      (node (ref "Q1") (pin "1") (pinfunction "A_1") (pintype "passive"))
    )
    (net (code "42") (name "unconnected-(Q3-A-Pad1)") (class "Default")
      (node (ref "Q3") (pin "1") (pinfunction "A_1") (pintype "passive"))
    )
    (net (code "43") (name "unconnected-(R_IN1-Pad1)") (class "Default")
      (node (ref "R_IN1") (pin "1") (pinfunction "1_1") (pintype "passive"))
    )
    (net (code "44") (name "unconnected-(R_IN3-Pad1)") (class "Default")
      (node (ref "R_IN3") (pin "1") (pinfunction "1_1") (pintype "passive"))
    )
    (net (code "45") (name "unconnected-(U2A-PA0-Pad34)") (class "Default")
      (node (ref "U2") (pin "34") (pinfunction "PA0_34") (pintype "passive"))
    )
    (net (code "46") (name "unconnected-(U2A-PA1-Pad35)") (class "Default")
      (node (ref "U2") (pin "35") (pinfunction "PA1_35") (pintype "passive"))
    )
    (net (code "47") (name "unconnected-(U2A-PA2-Pad36)") (class "Default")
      (node (ref "U2") (pin "36") (pinfunction "PA2_36") (pintype "passive"))
    )
    (net (code "48") (name "unconnected-(U2A-PA3-Pad37)") (class "Default")
      (node (ref "U2") (pin "37") (pinfunction "PA3_37") (pintype "passive"))
    )
    (net (code "49") (name "unconnected-(U2A-PA4-Pad40)") (class "Default")
      (node (ref "U2") (pin "40") (pinfunction "PA4_40") (pintype "passive"))
    )
    (net (code "50") (name "unconnected-(U2A-PA5-Pad41)") (class "Default")
      (node (ref "U2") (pin "41") (pinfunction "PA5_41") (pintype "passive"))
    )
    (net (code "51") (name "unconnected-(U2A-PA6-Pad42)") (class "Default")
      (node (ref "U2") (pin "42") (pinfunction "PA6_42") (pintype "passive"))
    )
    (net (code "52") (name "unconnected-(U2A-PA7-Pad43)") (class "Default")
      (node (ref "U2") (pin "43") (pinfunction "PA7_43") (pintype "passive"))
    )
    (net (code "53") (name "unconnected-(U2A-PA8-Pad100)") (class "Default")
      (node (ref "U2") (pin "100") (pinfunction "PA8_100") (pintype "passive"))
    )
    (net (code "54") (name "unconnected-(U2A-PA9-Pad101)") (class "Default")
      (node (ref "U2") (pin "101") (pinfunction "PA9_101") (pintype "passive"))
    )
    (net (code "55") (name "unconnected-(U2A-PA10-Pad102)") (class "Default")
      (node (ref "U2") (pin "102") (pinfunction "PA10_102") (pintype "passive"))
    )
    (net (code "56") (name "unconnected-(U2A-PA11-Pad103)") (class "Default")
      (node (ref "U2") (pin "103") (pinfunction "PA11_103") (pintype "passive"))
    )
    (net (code "57") (name "unconnected-(U2A-PA12-Pad104)") (class "Default")
      (node (ref "U2") (pin "104") (pinfunction "PA12_104") (pintype "passive"))
    )
    (net (code "58") (name "unconnected-(U2A-PA13-Pad105)") (class "Default")
      (node (ref "U2") (pin "105") (pinfunction "PA13_105") (pintype "passive"))
    )
    (net (code "59") (name "unconnected-(U2A-PA14-Pad109)") (class "Default")
      (node (ref "U2") (pin "109") (pinfunction "PA14_109") (pintype "passive"))
    )
    (net (code "60") (name "unconnected-(U2A-PA15-Pad110)") (class "Default")
      (node (ref "U2") (pin "110") (pinfunction "PA15_110") (pintype "passive"))
    )
    (net (code "61") (name "unconnected-(U2A-PB0-Pad46)") (class "Default")
      (node (ref "U2") (pin "46") (pinfunction "PB0_46") (pintype "passive"))
    )
    (net (code "62") (name "unconnected-(U2A-PB1-Pad47)") (class "Default")
      (node (ref "U2") (pin "47") (pinfunction "PB1_47") (pintype "passive"))
    )
    (net (code "63") (name "unconnected-(U2A-PB2-Pad48)") (class "Default")
      (node (ref "U2") (pin "48") (pinfunction "PB2_48") (pintype "passive"))
    )
    (net (code "64") (name "unconnected-(U2A-PB3-Pad133)") (class "Default")
      (node (ref "U2") (pin "133") (pinfunction "PB3_133") (pintype "bidirectional"))
    )
    (net (code "65") (name "unconnected-(U2A-PB4-Pad134)") (class "Default")
      (node (ref "U2") (pin "134") (pinfunction "PB4_134") (pintype "bidirectional"))
    )
    (net (code "66") (name "unconnected-(U2A-PB5-Pad135)") (class "Default")
      (node (ref "U2") (pin "135") (pinfunction "PB5_135") (pintype "bidirectional"))
    )
    (net (code "67") (name "unconnected-(U2A-PB6-Pad136)") (class "Default")
      (node (ref "U2") (pin "136") (pinfunction "PB6_136") (pintype "bidirectional"))
    )
    (net (code "68") (name "unconnected-(U2A-PB7-Pad137)") (class "Default")
      (node (ref "U2") (pin "137") (pinfunction "PB7_137") (pintype "bidirectional"))
    )
    (net (code "69") (name "unconnected-(U2A-PB8-Pad139)") (class "Default")
      (node (ref "U2") (pin "139") (pinfunction "PB8_139") (pintype "bidirectional"))
    )
    (net (code "70") (name "unconnected-(U2A-PB9-Pad140)") (class "Default")
      (node (ref "U2") (pin "140") (pinfunction "PB9_140") (pintype "bidirectional"))
    )
    (net (code "71") (name "unconnected-(U2A-PB10-Pad69)") (class "Default")
      (node (ref "U2") (pin "69") (pinfunction "PB10_69") (pintype "passive"))
    )
    (net (code "72") (name "unconnected-(U2A-PB11-Pad70)") (class "Default")
      (node (ref "U2") (pin "70") (pinfunction "PB11_70") (pintype "passive"))
    )
    (net (code "73") (name "unconnected-(U2A-PB12-Pad73)") (class "Default")
      (node (ref "U2") (pin "73") (pinfunction "PB12_73") (pintype "passive"))
    )
    (net (code "74") (name "unconnected-(U2A-PB13-Pad74)") (class "Default")
      (node (ref "U2") (pin "74") (pinfunction "PB13_74") (pintype "passive"))
    )
    (net (code "75") (name "unconnected-(U2A-PB14-Pad75)") (class "Default")
      (node (ref "U2") (pin "75") (pinfunction "PB14_75") (pintype "passive"))
    )
    (net (code "76") (name "unconnected-(U2A-PB15-Pad76)") (class "Default")
      (node (ref "U2") (pin "76") (pinfunction "PB15_76") (pintype "passive"))
    )
    (net (code "77") (name "unconnected-(U2A-PC0-Pad26)") (class "Default")
      (node (ref "U2") (pin "26") (pinfunction "PC0_26") (pintype "passive"))
    )
    (net (code "78") (name "unconnected-(U2A-PC9-Pad99)") (class "Default")
      (node (ref "U2") (pin "99") (pinfunction "PC9_99") (pintype "passive"))
    )
    (net (code "79") (name "unconnected-(U2A-PC10-Pad111)") (class "Default")
      (node (ref "U2") (pin "111") (pinfunction "PC10_111") (pintype "passive"))
    )
    (net (code "80") (name "unconnected-(U2A-PC11-Pad112)") (class "Default")
      (node (ref "U2") (pin "112") (pinfunction "PC11_112") (pintype "passive"))
    )
    (net (code "81") (name "unconnected-(U2A-PC12-Pad113)") (class "Default")
      (node (ref "U2") (pin "113") (pinfunction "PC12_113") (pintype "passive"))
    )
    (net (code "82") (name "unconnected-(U2A-PC13-Pad7)") (class "Default")
      (node (ref "U2") (pin "7") (pinfunction "PC13_7") (pintype "passive"))
    )
    (net (code "83") (name "unconnected-(U2A-PC14-Pad8)") (class "Default")
      (node (ref "U2") (pin "8") (pinfunction "PC14_8") (pintype "passive"))
    )
    (net (code "84") (name "unconnected-(U2A-PC15-Pad9)") (class "Default")
      (node (ref "U2") (pin "9") (pinfunction "PC15_9") (pintype "passive"))
    )
    (net (code "85") (name "unconnected-(U2A-PD0-Pad114)") (class "Default")
      (node (ref "U2") (pin "114") (pinfunction "PD0_114") (pintype "passive"))
    )
    (net (code "86") (name "unconnected-(U2A-PD1-Pad115)") (class "Default")
      (node (ref "U2") (pin "115") (pinfunction "PD1_115") (pintype "passive"))
    )
    (net (code "87") (name "unconnected-(U2A-PD2-Pad116)") (class "Default")
      (node (ref "U2") (pin "116") (pinfunction "PD2_116") (pintype "passive"))
    )
    (net (code "88") (name "unconnected-(U2A-PD3-Pad117)") (class "Default")
      (node (ref "U2") (pin "117") (pinfunction "PD3_117") (pintype "passive"))
    )
    (net (code "89") (name "unconnected-(U2A-PD4-Pad118)") (class "Default")
      (node (ref "U2") (pin "118") (pinfunction "PD4_118") (pintype "passive"))
    )
    (net (code "90") (name "unconnected-(U2A-PD5-Pad119)") (class "Default")
      (node (ref "U2") (pin "119") (pinfunction "PD5_119") (pintype "passive"))
    )
    (net (code "91") (name "unconnected-(U2A-PD6-Pad122)") (class "Default")
      (node (ref "U2") (pin "122") (pinfunction "PD6_122") (pintype "passive"))
    )
    (net (code "92") (name "unconnected-(U2A-PD7-Pad123)") (class "Default")
      (node (ref "U2") (pin "123") (pinfunction "PD7_123") (pintype "passive"))
    )
    (net (code "93") (name "unconnected-(U2A-PD8-Pad77)") (class "Default")
      (node (ref "U2") (pin "77") (pinfunction "PD8_77") (pintype "passive"))
    )
    (net (code "94") (name "unconnected-(U2A-PD9-Pad78)") (class "Default")
      (node (ref "U2") (pin "78") (pinfunction "PD9_78") (pintype "passive"))
    )
    (net (code "95") (name "unconnected-(U2A-PD10-Pad79)") (class "Default")
      (node (ref "U2") (pin "79") (pinfunction "PD10_79") (pintype "passive"))
    )
    (net (code "96") (name "unconnected-(U2A-PD11-Pad80)") (class "Default")
      (node (ref "U2") (pin "80") (pinfunction "PD11_80") (pintype "passive"))
    )
    (net (code "97") (name "unconnected-(U2A-PD12-Pad81)") (class "Default")
      (node (ref "U2") (pin "81") (pinfunction "PD12_81") (pintype "passive"))
    )
    (net (code "98") (name "unconnected-(U2A-PD13-Pad82)") (class "Default")
      (node (ref "U2") (pin "82") (pinfunction "PD13_82") (pintype "passive"))
    )
    (net (code "99") (name "unconnected-(U2A-PD14-Pad85)") (class "Default")
      (node (ref "U2") (pin "85") (pinfunction "PD14_85") (pintype "passive"))
    )
    (net (code "100") (name "unconnected-(U2A-PD15-Pad86)") (class "Default")
      (node (ref "U2") (pin "86") (pinfunction "PD15_86") (pintype "passive"))
    )
  )
)
